# 4_bootleg-ev-periferals.net
KiCad netlist of a schematic drawn in Altium Designer
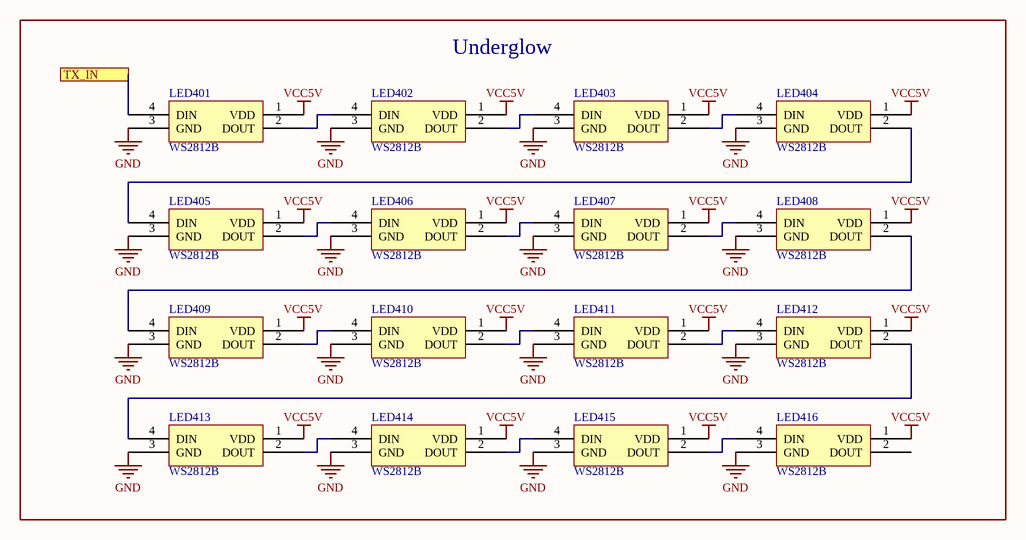
[diagram p0: 4_bootleg-ev-periferals.SchDoc]

(export (version "E")
  (design (tool "Eeschema 10.0.6"))
  (components
    (comp (ref "LED401")
      (value "WS2812B")
      (footprint "WS2812B - 2020")
      (fields (field (name "LCSC PART #") "C965555") (field (name "MRF.PART") "WS2812B-2020"))
      (libsource (lib "Keebs") (part "WS2812B"))
    )
    (comp (ref "LED402")
      (value "WS2812B")
      (footprint "WS2812B - 2020")
      (fields (field (name "LCSC PART #") "C965555") (field (name "MRF.PART") "WS2812B-2020"))
      (libsource (lib "Keebs") (part "WS2812B"))
    )
    (comp (ref "LED403")
      (value "WS2812B")
      (footprint "WS2812B - 2020")
      (fields (field (name "LCSC PART #") "C965555") (field (name "MRF.PART") "WS2812B-2020"))
      (libsource (lib "Keebs") (part "WS2812B"))
    )
    (comp (ref "LED404")
      (value "WS2812B")
      (footprint "WS2812B - 2020")
      (fields (field (name "LCSC PART #") "C965555") (field (name "MRF.PART") "WS2812B-2020"))
      (libsource (lib "Keebs") (part "WS2812B"))
    )
    (comp (ref "LED405")
      (value "WS2812B")
      (footprint "WS2812B - 2020")
      (fields (field (name "LCSC PART #") "C965555") (field (name "MRF.PART") "WS2812B-2020"))
      (libsource (lib "Keebs") (part "WS2812B"))
    )
    (comp (ref "LED406")
      (value "WS2812B")
      (footprint "WS2812B - 2020")
      (fields (field (name "LCSC PART #") "C965555") (field (name "MRF.PART") "WS2812B-2020"))
      (libsource (lib "Keebs") (part "WS2812B"))
    )
    (comp (ref "LED407")
      (value "WS2812B")
      (footprint "WS2812B - 2020")
      (fields (field (name "LCSC PART #") "C965555") (field (name "MRF.PART") "WS2812B-2020"))
      (libsource (lib "Keebs") (part "WS2812B"))
    )
    (comp (ref "LED408")
      (value "WS2812B")
      (footprint "WS2812B - 2020")
      (fields (field (name "LCSC PART #") "C965555") (field (name "MRF.PART") "WS2812B-2020"))
      (libsource (lib "Keebs") (part "WS2812B"))
    )
    (comp (ref "LED409")
      (value "WS2812B")
      (footprint "WS2812B - 2020")
      (fields (field (name "LCSC PART #") "C965555") (field (name "MRF.PART") "WS2812B-2020"))
      (libsource (lib "Keebs") (part "WS2812B"))
    )
    (comp (ref "LED410")
      (value "WS2812B")
      (footprint "WS2812B - 2020")
      (fields (field (name "LCSC PART #") "C965555") (field (name "MRF.PART") "WS2812B-2020"))
      (libsource (lib "Keebs") (part "WS2812B"))
    )
    (comp (ref "LED411")
      (value "WS2812B")
      (footprint "WS2812B - 2020")
      (fields (field (name "LCSC PART #") "C965555") (field (name "MRF.PART") "WS2812B-2020"))
      (libsource (lib "Keebs") (part "WS2812B"))
    )
    (comp (ref "LED412")
      (value "WS2812B")
      (footprint "WS2812B - 2020")
      (fields (field (name "LCSC PART #") "C965555") (field (name "MRF.PART") "WS2812B-2020"))
      (libsource (lib "Keebs") (part "WS2812B"))
    )
    (comp (ref "LED413")
      (value "WS2812B")
      (footprint "WS2812B - 2020")
      (fields (field (name "LCSC PART #") "C965555") (field (name "MRF.PART") "WS2812B-2020"))
      (libsource (lib "Keebs") (part "WS2812B"))
    )
    (comp (ref "LED414")
      (value "WS2812B")
      (footprint "WS2812B - 2020")
      (fields (field (name "LCSC PART #") "C965555") (field (name "MRF.PART") "WS2812B-2020"))
      (libsource (lib "Keebs") (part "WS2812B"))
    )
    (comp (ref "LED415")
      (value "WS2812B")
      (footprint "WS2812B - 2020")
      (fields (field (name "LCSC PART #") "C965555") (field (name "MRF.PART") "WS2812B-2020"))
      (libsource (lib "Keebs") (part "WS2812B"))
    )
    (comp (ref "LED416")
      (value "WS2812B")
      (footprint "WS2812B - 2020")
      (fields (field (name "LCSC PART #") "C965555") (field (name "MRF.PART") "WS2812B-2020"))
      (libsource (lib "Keebs") (part "WS2812B"))
    )
  )
  (nets
    (net (code "1") (name "/TX_IN") (class "Default")
      (node (ref "LED401") (pin "4") (pinfunction "DIN_4") (pintype "passive"))
    )
    (net (code "2") (name "GND") (class "Default")
      (node (ref "LED401") (pin "3") (pinfunction "GND_3") (pintype "passive"))
      (node (ref "LED402") (pin "3") (pinfunction "GND_3") (pintype "passive"))
      (node (ref "LED403") (pin "3") (pinfunction "GND_3") (pintype "passive"))
      (node (ref "LED404") (pin "3") (pinfunction "GND_3") (pintype "passive"))
      (node (ref "LED405") (pin "3") (pinfunction "GND_3") (pintype "passive"))
      (node (ref "LED406") (pin "3") (pinfunction "GND_3") (pintype "passive"))
      (node (ref "LED407") (pin "3") (pinfunction "GND_3") (pintype "passive"))
      (node (ref "LED408") (pin "3") (pinfunction "GND_3") (pintype "passive"))
      (node (ref "LED409") (pin "3") (pinfunction "GND_3") (pintype "passive"))
      (node (ref "LED410") (pin "3") (pinfunction "GND_3") (pintype "passive"))
      (node (ref "LED411") (pin "3") (pinfunction "GND_3") (pintype "passive"))
      (node (ref "LED412") (pin "3") (pinfunction "GND_3") (pintype "passive"))
      (node (ref "LED413") (pin "3") (pinfunction "GND_3") (pintype "passive"))
      (node (ref "LED414") (pin "3") (pinfunction "GND_3") (pintype "passive"))
      (node (ref "LED415") (pin "3") (pinfunction "GND_3") (pintype "passive"))
      (node (ref "LED416") (pin "3") (pinfunction "GND_3") (pintype "passive"))
    )
    (net (code "3") (name "Net-(LED401-DOUT)") (class "Default")
      (node (ref "LED401") (pin "2") (pinfunction "DOUT_2") (pintype "passive"))
      (node (ref "LED402") (pin "4") (pinfunction "DIN_4") (pintype "passive"))
    )
    (net (code "4") (name "Net-(LED402-DOUT)") (class "Default")
      (node (ref "LED402") (pin "2") (pinfunction "DOUT_2") (pintype "passive"))
      (node (ref "LED403") (pin "4") (pinfunction "DIN_4") (pintype "passive"))
    )
    (net (code "5") (name "Net-(LED403-DOUT)") (class "Default")
      (node (ref "LED403") (pin "2") (pinfunction "DOUT_2") (pintype "passive"))
      (node (ref "LED404") (pin "4") (pinfunction "DIN_4") (pintype "passive"))
    )
    (net (code "6") (name "Net-(LED404-DOUT)") (class "Default")
      (node (ref "LED404") (pin "2") (pinfunction "DOUT_2") (pintype "passive"))
      (node (ref "LED405") (pin "4") (pinfunction "DIN_4") (pintype "passive"))
    )
    (net (code "7") (name "Net-(LED405-DOUT)") (class "Default")
      (node (ref "LED405") (pin "2") (pinfunction "DOUT_2") (pintype "passive"))
      (node (ref "LED406") (pin "4") (pinfunction "DIN_4") (pintype "passive"))
    )
    (net (code "8") (name "Net-(LED406-DOUT)") (class "Default")
      (node (ref "LED406") (pin "2") (pinfunction "DOUT_2") (pintype "passive"))
      (node (ref "LED407") (pin "4") (pinfunction "DIN_4") (pintype "passive"))
    )
    (net (code "9") (name "Net-(LED407-DOUT)") (class "Default")
      (node (ref "LED407") (pin "2") (pinfunction "DOUT_2") (pintype "passive"))
      (node (ref "LED408") (pin "4") (pinfunction "DIN_4") (pintype "passive"))
    )
    (net (code "10") (name "Net-(LED408-DOUT)") (class "Default")
      (node (ref "LED408") (pin "2") (pinfunction "DOUT_2") (pintype "passive"))
      (node (ref "LED409") (pin "4") (pinfunction "DIN_4") (pintype "passive"))
    )
    (net (code "11") (name "Net-(LED409-DOUT)") (class "Default")
      (node (ref "LED409") (pin "2") (pinfunction "DOUT_2") (pintype "passive"))
      (node (ref "LED410") (pin "4") (pinfunction "DIN_4") (pintype "passive"))
    )
    (net (code "12") (name "Net-(LED410-DOUT)") (class "Default")
      (node (ref "LED410") (pin "2") (pinfunction "DOUT_2") (pintype "passive"))
      (node (ref "LED411") (pin "4") (pinfunction "DIN_4") (pintype "passive"))
    )
    (net (code "13") (name "Net-(LED411-DOUT)") (class "Default")
      (node (ref "LED411") (pin "2") (pinfunction "DOUT_2") (pintype "passive"))
      (node (ref "LED412") (pin "4") (pinfunction "DIN_4") (pintype "passive"))
    )
    (net (code "14") (name "Net-(LED412-DOUT)") (class "Default")
      (node (ref "LED412") (pin "2") (pinfunction "DOUT_2") (pintype "passive"))
      (node (ref "LED413") (pin "4") (pinfunction "DIN_4") (pintype "passive"))
    )
    (net (code "15") (name "Net-(LED413-DOUT)") (class "Default")
      (node (ref "LED413") (pin "2") (pinfunction "DOUT_2") (pintype "passive"))
      (node (ref "LED414") (pin "4") (pinfunction "DIN_4") (pintype "passive"))
    )
    (net (code "16") (name "Net-(LED414-DOUT)") (class "Default")
      (node (ref "LED414") (pin "2") (pinfunction "DOUT_2") (pintype "passive"))
      (node (ref "LED415") (pin "4") (pinfunction "DIN_4") (pintype "passive"))
    )
    (net (code "17") (name "Net-(LED415-DOUT)") (class "Default")
      (node (ref "LED415") (pin "2") (pinfunction "DOUT_2") (pintype "passive"))
      (node (ref "LED416") (pin "4") (pinfunction "DIN_4") (pintype "passive"))
    )
    (net (code "18") (name "VCC5V") (class "Default")
      (node (ref "LED401") (pin "1") (pinfunction "VDD_1") (pintype "passive"))
      (node (ref "LED402") (pin "1") (pinfunction "VDD_1") (pintype "passive"))
      (node (ref "LED403") (pin "1") (pinfunction "VDD_1") (pintype "passive"))
      (node (ref "LED404") (pin "1") (pinfunction "VDD_1") (pintype "passive"))
      (node (ref "LED405") (pin "1") (pinfunction "VDD_1") (pintype "passive"))
      (node (ref "LED406") (pin "1") (pinfunction "VDD_1") (pintype "passive"))
      (node (ref "LED407") (pin "1") (pinfunction "VDD_1") (pintype "passive"))
      (node (ref "LED408") (pin "1") (pinfunction "VDD_1") (pintype "passive"))
      (node (ref "LED409") (pin "1") (pinfunction "VDD_1") (pintype "passive"))
      (node (ref "LED410") (pin "1") (pinfunction "VDD_1") (pintype "passive"))
      (node (ref "LED411") (pin "1") (pinfunction "VDD_1") (pintype "passive"))
      (node (ref "LED412") (pin "1") (pinfunction "VDD_1") (pintype "passive"))
      (node (ref "LED413") (pin "1") (pinfunction "VDD_1") (pintype "passive"))
      (node (ref "LED414") (pin "1") (pinfunction "VDD_1") (pintype "passive"))
      (node (ref "LED415") (pin "1") (pinfunction "VDD_1") (pintype "passive"))
      (node (ref "LED416") (pin "1") (pinfunction "VDD_1") (pintype "passive"))
    )
    (net (code "19") (name "unconnected-(LED416-DOUT-Pad2)") (class "Default")
      (node (ref "LED416") (pin "2") (pinfunction "DOUT_2") (pintype "passive"))
    )
  )
)
